# birthdaydisplay.net
KiCad netlist of a schematic drawn in EAGLE
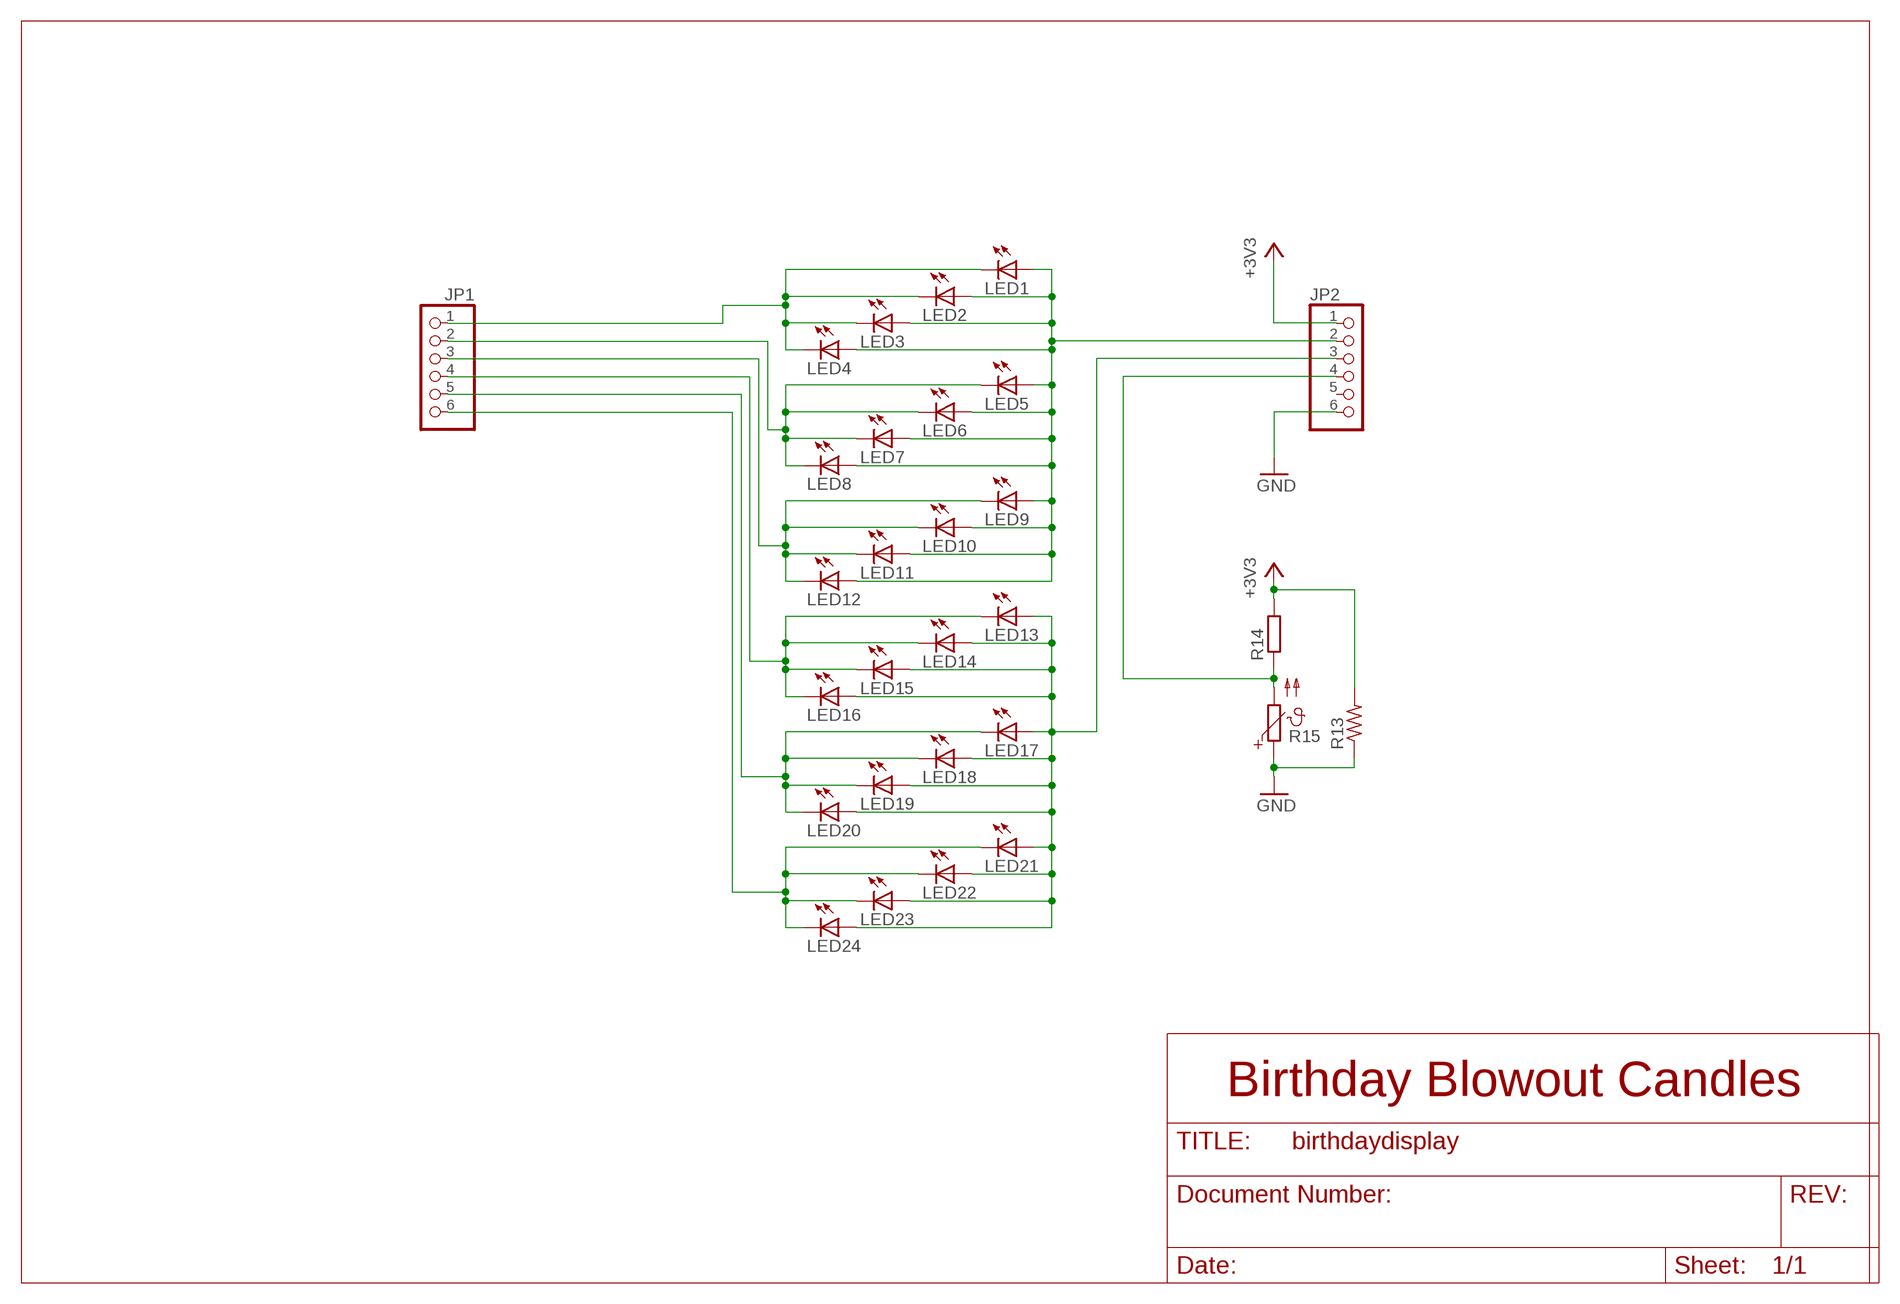
[diagram p0: schematic, sheet 1]

(export (version "E")
  (design (tool "Eeschema 10.0.6"))
  (components
    (comp (ref "JP1")
      (value "PINHD-1X6")
      (footprint "eagle-import:1X06")
      (libsource (lib "eagle-import") (part "PINHD-1X6"))
    )
    (comp (ref "JP2")
      (value "PINHD-1X6")
      (footprint "eagle-import:1X06")
      (libsource (lib "eagle-import") (part "PINHD-1X6"))
    )
    (comp (ref "LED1")
      (value "LED3MM")
      (footprint "eagle-import:LED3MM")
      (libsource (lib "eagle-import") (part "LED3MM"))
    )
    (comp (ref "LED2")
      (value "LED3MM")
      (footprint "eagle-import:LED3MM")
      (libsource (lib "eagle-import") (part "LED3MM"))
    )
    (comp (ref "LED3")
      (value "LED3MM")
      (footprint "eagle-import:LED3MM")
      (libsource (lib "eagle-import") (part "LED3MM"))
    )
    (comp (ref "LED4")
      (value "LED3MM")
      (footprint "eagle-import:LED3MM")
      (libsource (lib "eagle-import") (part "LED3MM"))
    )
    (comp (ref "LED5")
      (value "LED3MM")
      (footprint "eagle-import:LED3MM")
      (libsource (lib "eagle-import") (part "LED3MM"))
    )
    (comp (ref "LED6")
      (value "LED3MM")
      (footprint "eagle-import:LED3MM")
      (libsource (lib "eagle-import") (part "LED3MM"))
    )
    (comp (ref "LED7")
      (value "LED3MM")
      (footprint "eagle-import:LED3MM")
      (libsource (lib "eagle-import") (part "LED3MM"))
    )
    (comp (ref "LED8")
      (value "LED3MM")
      (footprint "eagle-import:LED3MM")
      (libsource (lib "eagle-import") (part "LED3MM"))
    )
    (comp (ref "LED9")
      (value "LED3MM")
      (footprint "eagle-import:LED3MM")
      (libsource (lib "eagle-import") (part "LED3MM"))
    )
    (comp (ref "LED10")
      (value "LED3MM")
      (footprint "eagle-import:LED3MM")
      (libsource (lib "eagle-import") (part "LED3MM"))
    )
    (comp (ref "LED11")
      (value "LED3MM")
      (footprint "eagle-import:LED3MM")
      (libsource (lib "eagle-import") (part "LED3MM"))
    )
    (comp (ref "LED12")
      (value "LED3MM")
      (footprint "eagle-import:LED3MM")
      (libsource (lib "eagle-import") (part "LED3MM"))
    )
    (comp (ref "LED13")
      (value "LED3MM")
      (footprint "eagle-import:LED3MM")
      (libsource (lib "eagle-import") (part "LED3MM"))
    )
    (comp (ref "LED14")
      (value "LED3MM")
      (footprint "eagle-import:LED3MM")
      (libsource (lib "eagle-import") (part "LED3MM"))
    )
    (comp (ref "LED15")
      (value "LED3MM")
      (footprint "eagle-import:LED3MM")
      (libsource (lib "eagle-import") (part "LED3MM"))
    )
    (comp (ref "LED16")
      (value "LED3MM")
      (footprint "eagle-import:LED3MM")
      (libsource (lib "eagle-import") (part "LED3MM"))
    )
    (comp (ref "LED17")
      (value "LED3MM")
      (footprint "eagle-import:LED3MM")
      (libsource (lib "eagle-import") (part "LED3MM"))
    )
    (comp (ref "LED18")
      (value "LED3MM")
      (footprint "eagle-import:LED3MM")
      (libsource (lib "eagle-import") (part "LED3MM"))
    )
    (comp (ref "LED19")
      (value "LED3MM")
      (footprint "eagle-import:LED3MM")
      (libsource (lib "eagle-import") (part "LED3MM"))
    )
    (comp (ref "LED20")
      (value "LED3MM")
      (footprint "eagle-import:LED3MM")
      (libsource (lib "eagle-import") (part "LED3MM"))
    )
    (comp (ref "LED21")
      (value "LED3MM")
      (footprint "eagle-import:LED3MM")
      (libsource (lib "eagle-import") (part "LED3MM"))
    )
    (comp (ref "LED22")
      (value "LED3MM")
      (footprint "eagle-import:LED3MM")
      (libsource (lib "eagle-import") (part "LED3MM"))
    )
    (comp (ref "LED23")
      (value "LED3MM")
      (footprint "eagle-import:LED3MM")
      (libsource (lib "eagle-import") (part "LED3MM"))
    )
    (comp (ref "LED24")
      (value "LED3MM")
      (footprint "eagle-import:LED3MM")
      (libsource (lib "eagle-import") (part "LED3MM"))
    )
    (comp (ref "R13")
      (value "R-US_0207/10")
      (footprint "eagle-import:0207_10")
      (libsource (lib "eagle-import") (part "R-US_0207/10"))
    )
    (comp (ref "R14")
      (value "R-EU_0207/7")
      (footprint "eagle-import:0207_7")
      (libsource (lib "eagle-import") (part "R-EU_0207/7"))
    )
    (comp (ref "R15")
      (value "PTC679")
      (footprint "eagle-import:P679")
      (libsource (lib "eagle-import") (part "PTC679"))
    )
  )
  (nets
    (net (code "1") (name "+3V3") (class "Default")
      (node (ref "JP2") (pin "1") (pinfunction "1_1") (pintype "passive"))
      (node (ref "R13") (pin "2") (pinfunction "2_2") (pintype "passive"))
      (node (ref "R14") (pin "2") (pinfunction "2_2") (pintype "passive"))
    )
    (net (code "2") (name "GND") (class "Default")
      (node (ref "JP2") (pin "6") (pinfunction "6_6") (pintype "passive"))
      (node (ref "R13") (pin "1") (pinfunction "1_1") (pintype "passive"))
      (node (ref "R15") (pin "1") (pinfunction "1_1") (pintype "passive"))
    )
    (net (code "3") (name "Net-(JP2-Pad2)") (class "Default")
      (node (ref "JP2") (pin "2") (pinfunction "2_2") (pintype "passive"))
      (node (ref "LED1") (pin "A") (pinfunction "A_A") (pintype "passive"))
      (node (ref "LED10") (pin "A") (pinfunction "A_A") (pintype "passive"))
      (node (ref "LED11") (pin "A") (pinfunction "A_A") (pintype "passive"))
      (node (ref "LED12") (pin "A") (pinfunction "A_A") (pintype "passive"))
      (node (ref "LED2") (pin "A") (pinfunction "A_A") (pintype "passive"))
      (node (ref "LED3") (pin "A") (pinfunction "A_A") (pintype "passive"))
      (node (ref "LED4") (pin "A") (pinfunction "A_A") (pintype "passive"))
      (node (ref "LED5") (pin "A") (pinfunction "A_A") (pintype "passive"))
      (node (ref "LED6") (pin "A") (pinfunction "A_A") (pintype "passive"))
      (node (ref "LED7") (pin "A") (pinfunction "A_A") (pintype "passive"))
      (node (ref "LED8") (pin "A") (pinfunction "A_A") (pintype "passive"))
      (node (ref "LED9") (pin "A") (pinfunction "A_A") (pintype "passive"))
    )
    (net (code "4") (name "Net-(JP2-Pad3)") (class "Default")
      (node (ref "JP2") (pin "3") (pinfunction "3_3") (pintype "passive"))
      (node (ref "LED13") (pin "A") (pinfunction "A_A") (pintype "passive"))
      (node (ref "LED14") (pin "A") (pinfunction "A_A") (pintype "passive"))
      (node (ref "LED15") (pin "A") (pinfunction "A_A") (pintype "passive"))
      (node (ref "LED16") (pin "A") (pinfunction "A_A") (pintype "passive"))
      (node (ref "LED17") (pin "A") (pinfunction "A_A") (pintype "passive"))
      (node (ref "LED18") (pin "A") (pinfunction "A_A") (pintype "passive"))
      (node (ref "LED19") (pin "A") (pinfunction "A_A") (pintype "passive"))
      (node (ref "LED20") (pin "A") (pinfunction "A_A") (pintype "passive"))
      (node (ref "LED21") (pin "A") (pinfunction "A_A") (pintype "passive"))
      (node (ref "LED22") (pin "A") (pinfunction "A_A") (pintype "passive"))
      (node (ref "LED23") (pin "A") (pinfunction "A_A") (pintype "passive"))
      (node (ref "LED24") (pin "A") (pinfunction "A_A") (pintype "passive"))
    )
    (net (code "5") (name "Net-(JP2-Pad4)") (class "Default")
      (node (ref "JP2") (pin "4") (pinfunction "4_4") (pintype "passive"))
      (node (ref "R14") (pin "1") (pinfunction "1_1") (pintype "passive"))
      (node (ref "R15") (pin "2") (pinfunction "2_2") (pintype "passive"))
    )
    (net (code "6") (name "Net-(LED1-C)") (class "Default")
      (node (ref "JP1") (pin "1") (pinfunction "1_1") (pintype "passive"))
      (node (ref "LED1") (pin "K") (pinfunction "C_K") (pintype "passive"))
      (node (ref "LED2") (pin "K") (pinfunction "C_K") (pintype "passive"))
      (node (ref "LED3") (pin "K") (pinfunction "C_K") (pintype "passive"))
      (node (ref "LED4") (pin "K") (pinfunction "C_K") (pintype "passive"))
    )
    (net (code "7") (name "Net-(LED5-C)") (class "Default")
      (node (ref "JP1") (pin "2") (pinfunction "2_2") (pintype "passive"))
      (node (ref "LED5") (pin "K") (pinfunction "C_K") (pintype "passive"))
      (node (ref "LED6") (pin "K") (pinfunction "C_K") (pintype "passive"))
      (node (ref "LED7") (pin "K") (pinfunction "C_K") (pintype "passive"))
      (node (ref "LED8") (pin "K") (pinfunction "C_K") (pintype "passive"))
    )
    (net (code "8") (name "Net-(LED10-C)") (class "Default")
      (node (ref "JP1") (pin "3") (pinfunction "3_3") (pintype "passive"))
      (node (ref "LED10") (pin "K") (pinfunction "C_K") (pintype "passive"))
      (node (ref "LED11") (pin "K") (pinfunction "C_K") (pintype "passive"))
      (node (ref "LED12") (pin "K") (pinfunction "C_K") (pintype "passive"))
      (node (ref "LED9") (pin "K") (pinfunction "C_K") (pintype "passive"))
    )
    (net (code "9") (name "Net-(LED13-C)") (class "Default")
      (node (ref "JP1") (pin "4") (pinfunction "4_4") (pintype "passive"))
      (node (ref "LED13") (pin "K") (pinfunction "C_K") (pintype "passive"))
      (node (ref "LED14") (pin "K") (pinfunction "C_K") (pintype "passive"))
      (node (ref "LED15") (pin "K") (pinfunction "C_K") (pintype "passive"))
      (node (ref "LED16") (pin "K") (pinfunction "C_K") (pintype "passive"))
    )
    (net (code "10") (name "Net-(LED17-C)") (class "Default")
      (node (ref "JP1") (pin "5") (pinfunction "5_5") (pintype "passive"))
      (node (ref "LED17") (pin "K") (pinfunction "C_K") (pintype "passive"))
      (node (ref "LED18") (pin "K") (pinfunction "C_K") (pintype "passive"))
      (node (ref "LED19") (pin "K") (pinfunction "C_K") (pintype "passive"))
      (node (ref "LED20") (pin "K") (pinfunction "C_K") (pintype "passive"))
    )
    (net (code "11") (name "Net-(LED21-C)") (class "Default")
      (node (ref "JP1") (pin "6") (pinfunction "6_6") (pintype "passive"))
      (node (ref "LED21") (pin "K") (pinfunction "C_K") (pintype "passive"))
      (node (ref "LED22") (pin "K") (pinfunction "C_K") (pintype "passive"))
      (node (ref "LED23") (pin "K") (pinfunction "C_K") (pintype "passive"))
      (node (ref "LED24") (pin "K") (pinfunction "C_K") (pintype "passive"))
    )
    (net (code "12") (name "unconnected-(JP2-Pad5)") (class "Default")
      (node (ref "JP2") (pin "5") (pinfunction "5_5") (pintype "passive"))
    )
  )
)
